# MMA8452Q.net
KiCad netlist of a schematic drawn in Altium Designer
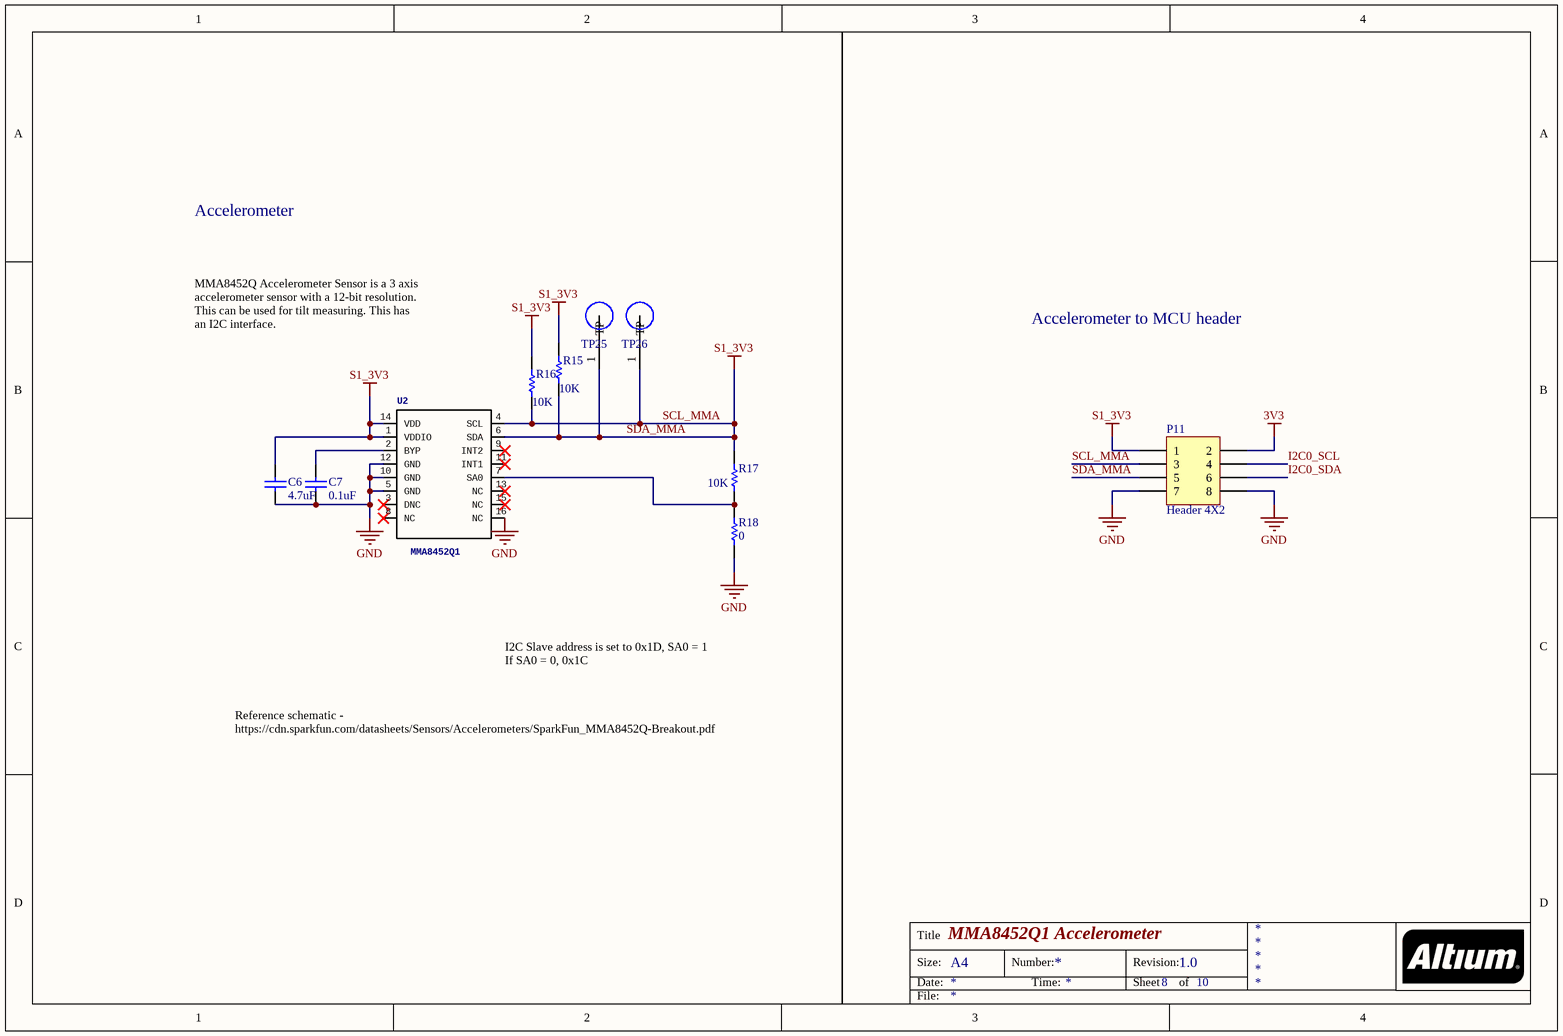
[diagram p0: MMA8452Q.SchDoc]

(export (version "E")
  (design (tool "Eeschema 10.0.6"))
  (components
    (comp (ref "C6")
      (value "4.7uF")
      (footprint "1608[0603]")
      (description "Capacitor")
      (fields
        (field (name "DIGI-KEY PART NUMBER") "1276-2087-1-ND")
        (field (name "MANUFACTURER") "Samsung Electro-Mechanics")
      )
      (libsource (lib "Miscellaneous Devices") (part "Cap"))
    )
    (comp (ref "C7")
      (value "0.1uF")
      (footprint "1608[0603]")
      (description "Capacitor")
      (fields
        (field (name "DIGI-KEY PART NUMBER") "1276-1005-1-ND")
        (field (name "MANUFACTURER") "Samsung Electro-Mechanics")
      )
      (libsource (lib "Miscellaneous Devices") (part "Cap"))
    )
    (comp (ref "P11")
      (value "Header 4X2")
      (footprint "4-PIN")
      (description "Header, 4-Pin, Dual row")
      (fields
        (field (name "DIGI-KEY PART NUMBER") "A121467-ND")
        (field (name "MANUFACTURER") "TE Connectivity")
      )
      (libsource (lib "Miscellaneous Connectors") (part "Header 4X2"))
    )
    (comp (ref "R15")
      (value "10K")
      (footprint "1608[0603]")
      (description "RES 10K OHM 1% 1/8W 0603")
      (fields
        (field (name "DIGI-KEY PART NUMBER") "RNCP0603FTD10K0CT-ND")
        (field (name "MANUFACTURER") "Stackpole Electronics Inc")
      )
      (libsource (lib "Miscellaneous Devices") (part "Res1"))
    )
    (comp (ref "R16")
      (value "10K")
      (footprint "1608[0603]")
      (description "RES 10K OHM 1% 1/8W 0603")
      (fields
        (field (name "DIGI-KEY PART NUMBER") "RNCP0603FTD10K0CT-ND")
        (field (name "MANUFACTURER") "Stackpole Electronics Inc")
      )
      (libsource (lib "Miscellaneous Devices") (part "Res1"))
    )
    (comp (ref "R17")
      (value "10K")
      (footprint "1608[0603]")
      (description "RES 10K OHM 1% 1/8W 0603")
      (fields
        (field (name "DIGI-KEY PART NUMBER") "RNCP0603FTD10K0CT-ND")
        (field (name "MANUFACTURER") "Stackpole Electronics Inc")
      )
      (libsource (lib "Miscellaneous Devices") (part "Res1"))
    )
    (comp (ref "R18")
      (value "0")
      (footprint "1608[0603]")
      (description "RES SMD 0 OHM JUMPER 1/10W 0603")
      (fields (field (name "DIGI-KEY PART NUMBER") "311-0.0GRCT-ND") (field (name "MANUFACTURER") "Yageo"))
      (libsource (lib "Miscellaneous Devices") (part "Res1"))
    )
    (comp (ref "TP25")
      (value "TP")
      (footprint "TP")
      (description "PC TEST POINT MINIATURE")
      (fields
        (field (name "MANUFACTURER") "Keystone Electronics")
        (field (name "DIGI-KEY PART NUMBER") "36-5019CT-ND")
      )
      (libsource (lib "TP") (part "TP"))
    )
    (comp (ref "TP26")
      (value "TP")
      (footprint "TP")
      (description "PC TEST POINT MINIATURE")
      (fields
        (field (name "MANUFACTURER") "Keystone Electronics")
        (field (name "DIGI-KEY PART NUMBER") "36-5019CT-ND")
      )
      (libsource (lib "TP") (part "TP"))
    )
    (comp (ref "U2")
      (value "MMA8452Q1")
      (footprint "MMA8452Q1")
      (description "ACCELEROMETER 2-8G I2C 16QFN")
      (fields
        (field (name "DIGI-KEY PART NUMBER") "MMA8452QR1CT-ND")
        (field (name "MANUFACTURER") "NXP USA Inc.")
      )
      (libsource (lib "Hydrated_Buffs") (part "MMA8452Q"))
    )
  )
  (nets
    (net (code "1") (name "/I2C0_SCL") (class "Default")
      (node (ref "P11") (pin "4") (pinfunction "4_4") (pintype "passive"))
    )
    (net (code "2") (name "/I2C0_SDA") (class "Default")
      (node (ref "P11") (pin "6") (pinfunction "6_6") (pintype "passive"))
    )
    (net (code "3") (name "3V3") (class "Default")
      (node (ref "P11") (pin "2") (pinfunction "2_2") (pintype "passive"))
    )
    (net (code "4") (name "GND") (class "Default")
      (node (ref "C6") (pin "1") (pinfunction "1_1") (pintype "passive"))
      (node (ref "C7") (pin "1") (pinfunction "1_1") (pintype "passive"))
      (node (ref "P11") (pin "7") (pinfunction "7_7") (pintype "passive"))
      (node (ref "P11") (pin "8") (pinfunction "8_8") (pintype "passive"))
      (node (ref "R18") (pin "1") (pinfunction "1_1") (pintype "passive"))
      (node (ref "U2") (pin "10") (pinfunction "GND_10") (pintype "passive"))
      (node (ref "U2") (pin "12") (pinfunction "GND_12") (pintype "passive"))
      (node (ref "U2") (pin "16") (pinfunction "NC_16") (pintype "passive"))
      (node (ref "U2") (pin "5") (pinfunction "GND_5") (pintype "passive"))
    )
    (net (code "5") (name "Net-(U2-BYP)") (class "Default")
      (node (ref "C7") (pin "2") (pinfunction "2_2") (pintype "passive"))
      (node (ref "U2") (pin "2") (pinfunction "BYP_2") (pintype "passive"))
    )
    (net (code "6") (name "Net-(U2-SA0)") (class "Default")
      (node (ref "R17") (pin "1") (pinfunction "1_1") (pintype "passive"))
      (node (ref "R18") (pin "2") (pinfunction "2_2") (pintype "passive"))
      (node (ref "U2") (pin "7") (pinfunction "SA0_7") (pintype "passive"))
    )
    (net (code "7") (name "S1_3V3") (class "Default")
      (node (ref "C6") (pin "2") (pinfunction "2_2") (pintype "passive"))
      (node (ref "P11") (pin "1") (pinfunction "1_1") (pintype "passive"))
      (node (ref "P11") (pin "3") (pinfunction "3_3") (pintype "passive"))
      (node (ref "P11") (pin "5") (pinfunction "5_5") (pintype "passive"))
      (node (ref "R15") (pin "1") (pinfunction "1_1") (pintype "passive"))
      (node (ref "R15") (pin "2") (pinfunction "2_2") (pintype "passive"))
      (node (ref "R16") (pin "1") (pinfunction "1_1") (pintype "passive"))
      (node (ref "R16") (pin "2") (pinfunction "2_2") (pintype "passive"))
      (node (ref "R17") (pin "2") (pinfunction "2_2") (pintype "passive"))
      (node (ref "TP25") (pin "1") (pinfunction "TP_1") (pintype "passive"))
      (node (ref "TP26") (pin "1") (pinfunction "TP_1") (pintype "passive"))
      (node (ref "U2") (pin "1") (pinfunction "VDDIO_1") (pintype "passive"))
      (node (ref "U2") (pin "14") (pinfunction "VDD_14") (pintype "passive"))
      (node (ref "U2") (pin "4") (pinfunction "SCL_4") (pintype "passive"))
      (node (ref "U2") (pin "6") (pinfunction "SDA_6") (pintype "passive"))
    )
    (net (code "8") (name "unconnected-(U2-DNC-Pad3)") (class "Default")
      (node (ref "U2") (pin "3") (pinfunction "DNC_3") (pintype "passive+no_connect"))
    )
    (net (code "9") (name "unconnected-(U2-INT1-Pad11)") (class "Default")
      (node (ref "U2") (pin "11") (pinfunction "INT1_11") (pintype "passive+no_connect"))
    )
    (net (code "10") (name "unconnected-(U2-INT2-Pad9)") (class "Default")
      (node (ref "U2") (pin "9") (pinfunction "INT2_9") (pintype "passive+no_connect"))
    )
    (net (code "11") (name "unconnected-(U2-NC-Pad8)") (class "Default")
      (node (ref "U2") (pin "8") (pinfunction "NC_8") (pintype "passive+no_connect"))
    )
    (net (code "12") (name "unconnected-(U2-NC-Pad13)") (class "Default")
      (node (ref "U2") (pin "13") (pinfunction "NC_13") (pintype "passive+no_connect"))
    )
    (net (code "13") (name "unconnected-(U2-NC-Pad15)") (class "Default")
      (node (ref "U2") (pin "15") (pinfunction "NC_15") (pintype "passive+no_connect"))
    )
  )
)
